# PFIL.net
KiCad netlist of a schematic drawn in Altium Designer
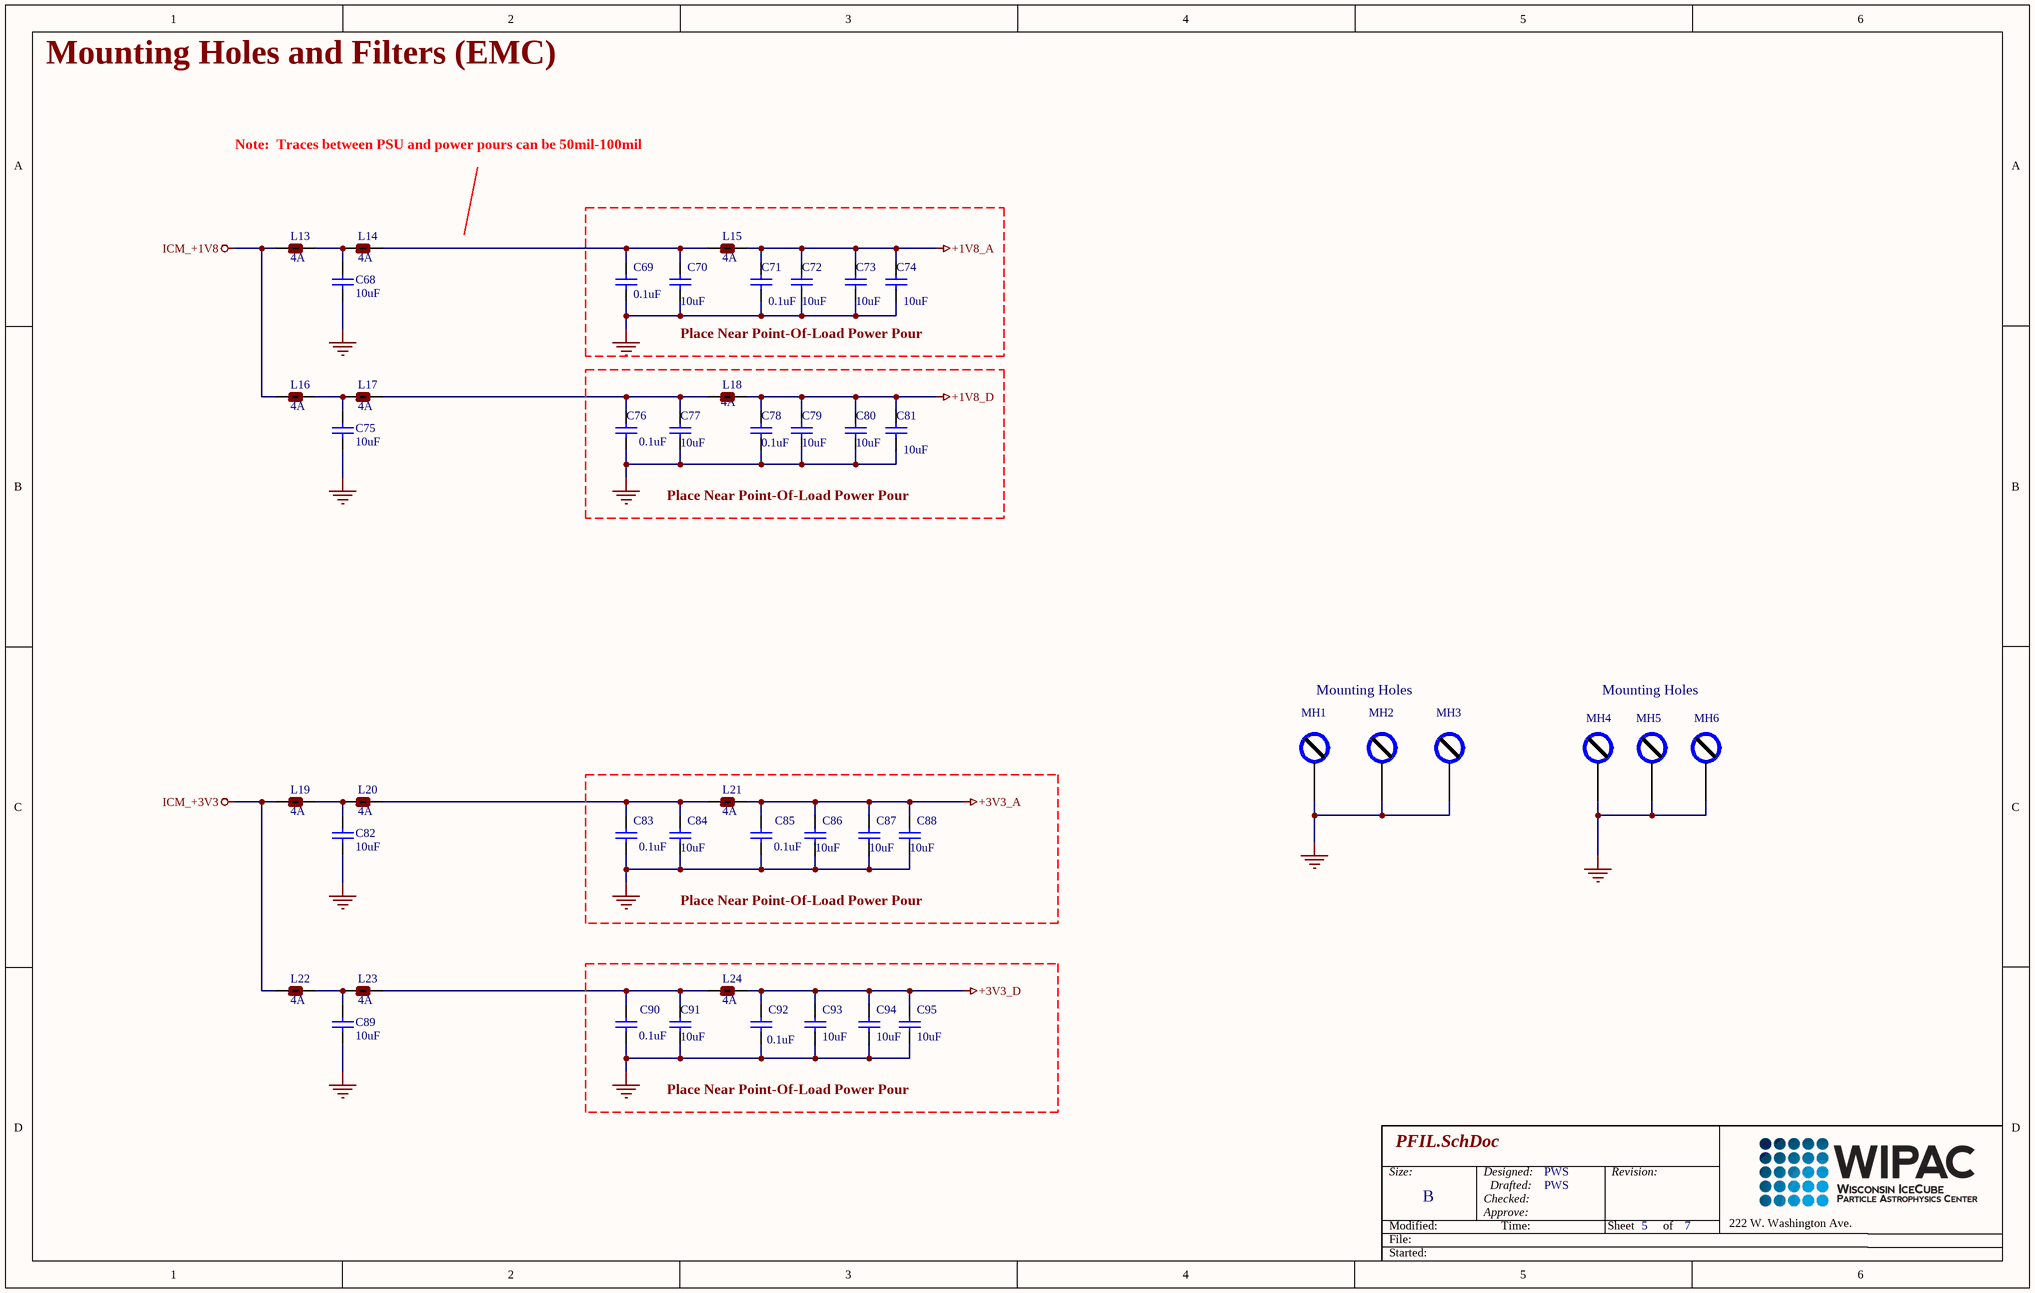
[diagram p0: PFIL.SchDoc]

(export (version "E")
  (design (tool "Eeschema 10.0.6"))
  (components
    (comp (ref "C68")
      (value "10uF_805_10V")
      (footprint "CAPC_0805")
      (description "Capacitor")
      (fields
        (field (name "MANUFACTURER") "Murata")
        (field (name "MANUFACTURER PART NUMBER") "GCJ21BR71A106KE01L")
        (field (name "CAPACITANCE") "10uF")
      )
      (libsource (lib "Custom1") (part "CapC_10uF_805_10V"))
    )
    (comp (ref "C69")
      (value "0.1uF_603_50V")
      (footprint "CAPC_0603")
      (description "0.1µF ±10% 50V Ceramic Capacitor X7R 0603 (1608 Metric)")
      (fields
        (field (name "MANUFACTURER") "Murata")
        (field (name "MANUFACTURER PART NUMBER") "GCJ188R71H104KA12D")
        (field (name "CAPACITANCE") "0.1uF")
      )
      (libsource (lib "Custom1") (part "CapC_0.1uF_603_50V_GCJ"))
    )
    (comp (ref "C70")
      (value "10uF_805_10V")
      (footprint "CAPC_0805")
      (description "Capacitor")
      (fields
        (field (name "MANUFACTURER") "Murata")
        (field (name "MANUFACTURER PART NUMBER") "GCJ21BR71A106KE01L")
        (field (name "CAPACITANCE") "10uF")
      )
      (libsource (lib "Custom1") (part "CapC_10uF_805_10V"))
    )
    (comp (ref "C71")
      (value "0.1uF_603_50V")
      (footprint "CAPC_0603")
      (description "0.1µF ±10% 50V Ceramic Capacitor X7R 0603 (1608 Metric)")
      (fields
        (field (name "MANUFACTURER") "Murata")
        (field (name "MANUFACTURER PART NUMBER") "GCJ188R71H104KA12D")
        (field (name "CAPACITANCE") "0.1uF")
      )
      (libsource (lib "Custom1") (part "CapC_0.1uF_603_50V_GCJ"))
    )
    (comp (ref "C72")
      (value "10uF_805_10V")
      (footprint "CAPC_0805")
      (description "Capacitor")
      (fields
        (field (name "MANUFACTURER") "Murata")
        (field (name "MANUFACTURER PART NUMBER") "GCJ21BR71A106KE01L")
        (field (name "CAPACITANCE") "10uF")
      )
      (libsource (lib "Custom1") (part "CapC_10uF_805_10V"))
    )
    (comp (ref "C73")
      (value "10uF_805_10V")
      (footprint "CAPC_0805")
      (description "Capacitor")
      (fields
        (field (name "MANUFACTURER") "Murata")
        (field (name "MANUFACTURER PART NUMBER") "GCJ21BR71A106KE01L")
        (field (name "CAPACITANCE") "10uF")
      )
      (libsource (lib "Custom1") (part "CapC_10uF_805_10V"))
    )
    (comp (ref "C74")
      (value "10uF_805_10V")
      (footprint "CAPC_0805")
      (description "Capacitor")
      (fields
        (field (name "MANUFACTURER") "Murata")
        (field (name "MANUFACTURER PART NUMBER") "GCJ21BR71A106KE01L")
        (field (name "CAPACITANCE") "10uF")
      )
      (libsource (lib "Custom1") (part "CapC_10uF_805_10V"))
    )
    (comp (ref "C75")
      (value "10uF_805_10V")
      (footprint "CAPC_0805")
      (description "Capacitor")
      (fields
        (field (name "MANUFACTURER") "Murata")
        (field (name "MANUFACTURER PART NUMBER") "GCJ21BR71A106KE01L")
        (field (name "CAPACITANCE") "10uF")
      )
      (libsource (lib "Custom1") (part "CapC_10uF_805_10V"))
    )
    (comp (ref "C76")
      (value "0.1uF_603_50V")
      (footprint "CAPC_0603")
      (description "0.1µF ±10% 50V Ceramic Capacitor X7R 0603 (1608 Metric)")
      (fields
        (field (name "MANUFACTURER") "Murata")
        (field (name "MANUFACTURER PART NUMBER") "GCJ188R71H104KA12D")
        (field (name "CAPACITANCE") "0.1uF")
      )
      (libsource (lib "Custom1") (part "CapC_0.1uF_603_50V_GCJ"))
    )
    (comp (ref "C77")
      (value "10uF_805_10V")
      (footprint "CAPC_0805")
      (description "Capacitor")
      (fields
        (field (name "MANUFACTURER") "Murata")
        (field (name "MANUFACTURER PART NUMBER") "GCJ21BR71A106KE01L")
        (field (name "CAPACITANCE") "10uF")
      )
      (libsource (lib "Custom1") (part "CapC_10uF_805_10V"))
    )
    (comp (ref "C78")
      (value "0.1uF_603_50V")
      (footprint "CAPC_0603")
      (description "0.1µF ±10% 50V Ceramic Capacitor X7R 0603 (1608 Metric)")
      (fields
        (field (name "MANUFACTURER") "Murata")
        (field (name "MANUFACTURER PART NUMBER") "GCJ188R71H104KA12D")
        (field (name "CAPACITANCE") "0.1uF")
      )
      (libsource (lib "Custom1") (part "CapC_0.1uF_603_50V_GCJ"))
    )
    (comp (ref "C79")
      (value "10uF_805_10V")
      (footprint "CAPC_0805")
      (description "Capacitor")
      (fields
        (field (name "MANUFACTURER") "Murata")
        (field (name "MANUFACTURER PART NUMBER") "GCJ21BR71A106KE01L")
        (field (name "CAPACITANCE") "10uF")
      )
      (libsource (lib "Custom1") (part "CapC_10uF_805_10V"))
    )
    (comp (ref "C80")
      (value "10uF_805_10V")
      (footprint "CAPC_0805")
      (description "Capacitor")
      (fields
        (field (name "MANUFACTURER") "Murata")
        (field (name "MANUFACTURER PART NUMBER") "GCJ21BR71A106KE01L")
        (field (name "CAPACITANCE") "10uF")
      )
      (libsource (lib "Custom1") (part "CapC_10uF_805_10V"))
    )
    (comp (ref "C81")
      (value "10uF_805_10V")
      (footprint "CAPC_0805")
      (description "Capacitor")
      (fields
        (field (name "MANUFACTURER") "Murata")
        (field (name "MANUFACTURER PART NUMBER") "GCJ21BR71A106KE01L")
        (field (name "CAPACITANCE") "10uF")
      )
      (libsource (lib "Custom1") (part "CapC_10uF_805_10V"))
    )
    (comp (ref "C82")
      (value "10uF_805_10V")
      (footprint "CAPC_0805")
      (description "Capacitor")
      (fields
        (field (name "MANUFACTURER") "Murata")
        (field (name "MANUFACTURER PART NUMBER") "GCJ21BR71A106KE01L")
        (field (name "CAPACITANCE") "10uF")
      )
      (libsource (lib "Custom1") (part "CapC_10uF_805_10V"))
    )
    (comp (ref "C83")
      (value "0.1uF_603_50V")
      (footprint "CAPC_0603")
      (description "0.1µF ±10% 50V Ceramic Capacitor X7R 0603 (1608 Metric)")
      (fields
        (field (name "MANUFACTURER") "Murata")
        (field (name "MANUFACTURER PART NUMBER") "GCJ188R71H104KA12D")
        (field (name "CAPACITANCE") "0.1uF")
      )
      (libsource (lib "Custom1") (part "CapC_0.1uF_603_50V_GCJ"))
    )
    (comp (ref "C84")
      (value "10uF_805_10V")
      (footprint "CAPC_0805")
      (description "Capacitor")
      (fields
        (field (name "MANUFACTURER") "Murata")
        (field (name "MANUFACTURER PART NUMBER") "GCJ21BR71A106KE01L")
        (field (name "CAPACITANCE") "10uF")
      )
      (libsource (lib "Custom1") (part "CapC_10uF_805_10V"))
    )
    (comp (ref "C85")
      (value "0.1uF_603_50V")
      (footprint "CAPC_0603")
      (description "0.1µF ±10% 50V Ceramic Capacitor X7R 0603 (1608 Metric)")
      (fields
        (field (name "MANUFACTURER") "Murata")
        (field (name "MANUFACTURER PART NUMBER") "GCJ188R71H104KA12D")
        (field (name "CAPACITANCE") "0.1uF")
      )
      (libsource (lib "Custom1") (part "CapC_0.1uF_603_50V_GCJ"))
    )
    (comp (ref "C86")
      (value "10uF_805_10V")
      (footprint "CAPC_0805")
      (description "Capacitor")
      (fields
        (field (name "MANUFACTURER") "Murata")
        (field (name "MANUFACTURER PART NUMBER") "GCJ21BR71A106KE01L")
        (field (name "CAPACITANCE") "10uF")
      )
      (libsource (lib "Custom1") (part "CapC_10uF_805_10V"))
    )
    (comp (ref "C87")
      (value "10uF_805_10V")
      (footprint "CAPC_0805")
      (description "Capacitor")
      (fields
        (field (name "MANUFACTURER") "Murata")
        (field (name "MANUFACTURER PART NUMBER") "GCJ21BR71A106KE01L")
        (field (name "CAPACITANCE") "10uF")
      )
      (libsource (lib "Custom1") (part "CapC_10uF_805_10V"))
    )
    (comp (ref "C88")
      (value "10uF_805_10V")
      (footprint "CAPC_0805")
      (description "Capacitor")
      (fields
        (field (name "MANUFACTURER") "Murata")
        (field (name "MANUFACTURER PART NUMBER") "GCJ21BR71A106KE01L")
        (field (name "CAPACITANCE") "10uF")
      )
      (libsource (lib "Custom1") (part "CapC_10uF_805_10V"))
    )
    (comp (ref "C89")
      (value "10uF_805_10V")
      (footprint "CAPC_0805")
      (description "Capacitor")
      (fields
        (field (name "MANUFACTURER") "Murata")
        (field (name "MANUFACTURER PART NUMBER") "GCJ21BR71A106KE01L")
        (field (name "CAPACITANCE") "10uF")
      )
      (libsource (lib "Custom1") (part "CapC_10uF_805_10V"))
    )
    (comp (ref "C90")
      (value "0.1uF_603_50V")
      (footprint "CAPC_0603")
      (description "0.1µF ±10% 50V Ceramic Capacitor X7R 0603 (1608 Metric)")
      (fields
        (field (name "MANUFACTURER") "Murata")
        (field (name "MANUFACTURER PART NUMBER") "GCJ188R71H104KA12D")
        (field (name "CAPACITANCE") "0.1uF")
      )
      (libsource (lib "Custom1") (part "CapC_0.1uF_603_50V_GCJ"))
    )
    (comp (ref "C91")
      (value "10uF_805_10V")
      (footprint "CAPC_0805")
      (description "Capacitor")
      (fields
        (field (name "MANUFACTURER") "Murata")
        (field (name "MANUFACTURER PART NUMBER") "GCJ21BR71A106KE01L")
        (field (name "CAPACITANCE") "10uF")
      )
      (libsource (lib "Custom1") (part "CapC_10uF_805_10V"))
    )
    (comp (ref "C92")
      (value "0.1uF_603_50V")
      (footprint "CAPC_0603")
      (description "0.1µF ±10% 50V Ceramic Capacitor X7R 0603 (1608 Metric)")
      (fields
        (field (name "MANUFACTURER") "Murata")
        (field (name "MANUFACTURER PART NUMBER") "GCJ188R71H104KA12D")
        (field (name "CAPACITANCE") "0.1uF")
      )
      (libsource (lib "Custom1") (part "CapC_0.1uF_603_50V_GCJ"))
    )
    (comp (ref "C93")
      (value "10uF_805_10V")
      (footprint "CAPC_0805")
      (description "Capacitor")
      (fields
        (field (name "MANUFACTURER") "Murata")
        (field (name "MANUFACTURER PART NUMBER") "GCJ21BR71A106KE01L")
        (field (name "CAPACITANCE") "10uF")
      )
      (libsource (lib "Custom1") (part "CapC_10uF_805_10V"))
    )
    (comp (ref "C94")
      (value "10uF_805_10V")
      (footprint "CAPC_0805")
      (description "Capacitor")
      (fields
        (field (name "MANUFACTURER") "Murata")
        (field (name "MANUFACTURER PART NUMBER") "GCJ21BR71A106KE01L")
        (field (name "CAPACITANCE") "10uF")
      )
      (libsource (lib "Custom1") (part "CapC_10uF_805_10V"))
    )
    (comp (ref "C95")
      (value "10uF_805_10V")
      (footprint "CAPC_0805")
      (description "Capacitor")
      (fields
        (field (name "MANUFACTURER") "Murata")
        (field (name "MANUFACTURER PART NUMBER") "GCJ21BR71A106KE01L")
        (field (name "CAPACITANCE") "10uF")
      )
      (libsource (lib "Custom1") (part "CapC_10uF_805_10V"))
    )
    (comp (ref "L13")
      (value "4.0A_Bead_0805")
      (footprint "SMD-0805")
      (description "100 Ohms @ 100MHz 1 Power Line Ferrite Bead 0805 (2012 Metric) 4A 20mOhm")
      (fields
        (field (name "MANUFACTURER") "TDK")
        (field (name "MANUFACTURER PART NUMBER") "MPZ2012S101ATD25")
        (field (name "MAX DC CURRENT") "4A")
      )
      (libsource (lib "Custom1") (part "Bead SM_805_4.0A_TDK"))
    )
    (comp (ref "L14")
      (value "4.0A_Bead_0805")
      (footprint "SMD-0805")
      (description "100 Ohms @ 100MHz 1 Power Line Ferrite Bead 0805 (2012 Metric) 4A 20mOhm")
      (fields
        (field (name "MANUFACTURER") "TDK")
        (field (name "MANUFACTURER PART NUMBER") "MPZ2012S101ATD25")
        (field (name "MAX DC CURRENT") "4A")
      )
      (libsource (lib "Custom1") (part "Bead SM_805_4.0A_TDK"))
    )
    (comp (ref "L15")
      (value "4.0A_Bead_0805")
      (footprint "SMD-0805")
      (description "100 Ohms @ 100MHz 1 Power Line Ferrite Bead 0805 (2012 Metric) 4A 20mOhm")
      (fields
        (field (name "MANUFACTURER") "TDK")
        (field (name "MANUFACTURER PART NUMBER") "MPZ2012S101ATD25")
        (field (name "MAX DC CURRENT") "4A")
      )
      (libsource (lib "Custom1") (part "Bead SM_805_4.0A_TDK"))
    )
    (comp (ref "L16")
      (value "4.0A_Bead_0805")
      (footprint "SMD-0805")
      (description "100 Ohms @ 100MHz 1 Power Line Ferrite Bead 0805 (2012 Metric) 4A 20mOhm")
      (fields
        (field (name "MANUFACTURER") "TDK")
        (field (name "MANUFACTURER PART NUMBER") "MPZ2012S101ATD25")
        (field (name "MAX DC CURRENT") "4A")
      )
      (libsource (lib "Custom1") (part "Bead SM_805_4.0A_TDK"))
    )
    (comp (ref "L17")
      (value "4.0A_Bead_0805")
      (footprint "SMD-0805")
      (description "100 Ohms @ 100MHz 1 Power Line Ferrite Bead 0805 (2012 Metric) 4A 20mOhm")
      (fields
        (field (name "MANUFACTURER") "TDK")
        (field (name "MANUFACTURER PART NUMBER") "MPZ2012S101ATD25")
        (field (name "MAX DC CURRENT") "4A")
      )
      (libsource (lib "Custom1") (part "Bead SM_805_4.0A_TDK"))
    )
    (comp (ref "L18")
      (value "4.0A_Bead_0805")
      (footprint "SMD-0805")
      (description "100 Ohms @ 100MHz 1 Power Line Ferrite Bead 0805 (2012 Metric) 4A 20mOhm")
      (fields
        (field (name "MANUFACTURER") "TDK")
        (field (name "MANUFACTURER PART NUMBER") "MPZ2012S101ATD25")
        (field (name "MAX DC CURRENT") "4A")
      )
      (libsource (lib "Custom1") (part "Bead SM_805_4.0A_TDK"))
    )
    (comp (ref "L19")
      (value "4.0A_Bead_0805")
      (footprint "SMD-0805")
      (description "100 Ohms @ 100MHz 1 Power Line Ferrite Bead 0805 (2012 Metric) 4A 20mOhm")
      (fields
        (field (name "MANUFACTURER") "TDK")
        (field (name "MANUFACTURER PART NUMBER") "MPZ2012S101ATD25")
        (field (name "MAX DC CURRENT") "4A")
      )
      (libsource (lib "Custom1") (part "Bead SM_805_4.0A_TDK"))
    )
    (comp (ref "L20")
      (value "4.0A_Bead_0805")
      (footprint "SMD-0805")
      (description "100 Ohms @ 100MHz 1 Power Line Ferrite Bead 0805 (2012 Metric) 4A 20mOhm")
      (fields
        (field (name "MANUFACTURER") "TDK")
        (field (name "MANUFACTURER PART NUMBER") "MPZ2012S101ATD25")
        (field (name "MAX DC CURRENT") "4A")
      )
      (libsource (lib "Custom1") (part "Bead SM_805_4.0A_TDK"))
    )
    (comp (ref "L21")
      (value "4.0A_Bead_0805")
      (footprint "SMD-0805")
      (description "100 Ohms @ 100MHz 1 Power Line Ferrite Bead 0805 (2012 Metric) 4A 20mOhm")
      (fields
        (field (name "MANUFACTURER") "TDK")
        (field (name "MANUFACTURER PART NUMBER") "MPZ2012S101ATD25")
        (field (name "MAX DC CURRENT") "4A")
      )
      (libsource (lib "Custom1") (part "Bead SM_805_4.0A_TDK"))
    )
    (comp (ref "L22")
      (value "4.0A_Bead_0805")
      (footprint "SMD-0805")
      (description "100 Ohms @ 100MHz 1 Power Line Ferrite Bead 0805 (2012 Metric) 4A 20mOhm")
      (fields
        (field (name "MANUFACTURER") "TDK")
        (field (name "MANUFACTURER PART NUMBER") "MPZ2012S101ATD25")
        (field (name "MAX DC CURRENT") "4A")
      )
      (libsource (lib "Custom1") (part "Bead SM_805_4.0A_TDK"))
    )
    (comp (ref "L23")
      (value "4.0A_Bead_0805")
      (footprint "SMD-0805")
      (description "100 Ohms @ 100MHz 1 Power Line Ferrite Bead 0805 (2012 Metric) 4A 20mOhm")
      (fields
        (field (name "MANUFACTURER") "TDK")
        (field (name "MANUFACTURER PART NUMBER") "MPZ2012S101ATD25")
        (field (name "MAX DC CURRENT") "4A")
      )
      (libsource (lib "Custom1") (part "Bead SM_805_4.0A_TDK"))
    )
    (comp (ref "L24")
      (value "4.0A_Bead_0805")
      (footprint "SMD-0805")
      (description "100 Ohms @ 100MHz 1 Power Line Ferrite Bead 0805 (2012 Metric) 4A 20mOhm")
      (fields
        (field (name "MANUFACTURER") "TDK")
        (field (name "MANUFACTURER PART NUMBER") "MPZ2012S101ATD25")
        (field (name "MAX DC CURRENT") "4A")
      )
      (libsource (lib "Custom1") (part "Bead SM_805_4.0A_TDK"))
    )
    (comp (ref "MH1")
      (value "Mounting Hole")
      (footprint "Mounting Pad #4 - Standoff")
      (libsource (lib "Custom1") (part "Mounting Hole #4_Standoff"))
    )
    (comp (ref "MH2")
      (value "Mounting Hole")
      (footprint "Mounting Pad #4 - Standoff")
      (libsource (lib "Custom1") (part "Mounting Hole #4_Standoff"))
    )
    (comp (ref "MH3")
      (value "Mounting Hole")
      (footprint "Mounting Pad #4 - Standoff")
      (libsource (lib "Custom1") (part "Mounting Hole #4_Standoff"))
    )
    (comp (ref "MH4")
      (value "Mounting Hole")
      (footprint "Mounting Pad #4 - Standoff")
      (libsource (lib "Custom1") (part "Mounting Hole #4_Standoff"))
    )
    (comp (ref "MH5")
      (value "Mounting Hole")
      (footprint "Mounting Pad #4 - Standoff")
      (libsource (lib "Custom1") (part "Mounting Hole #4_Standoff"))
    )
    (comp (ref "MH6")
      (value "Mounting Hole")
      (footprint "Mounting Pad #4 - Standoff")
      (libsource (lib "Custom1") (part "Mounting Hole #4_Standoff"))
    )
  )
  (nets
    (net (code "1") (name "+1V8_A") (class "Default")
      (node (ref "C71") (pin "2") (pinfunction "2_2") (pintype "passive"))
      (node (ref "C72") (pin "2") (pinfunction "2_2") (pintype "passive"))
      (node (ref "C73") (pin "2") (pinfunction "2_2") (pintype "passive"))
      (node (ref "C74") (pin "2") (pinfunction "2_2") (pintype "passive"))
      (node (ref "L15") (pin "2") (pinfunction "2_2") (pintype "passive"))
    )
    (net (code "2") (name "+1V8_D") (class "Default")
      (node (ref "C78") (pin "2") (pinfunction "2_2") (pintype "passive"))
      (node (ref "C79") (pin "2") (pinfunction "2_2") (pintype "passive"))
      (node (ref "C80") (pin "2") (pinfunction "2_2") (pintype "passive"))
      (node (ref "C81") (pin "2") (pinfunction "2_2") (pintype "passive"))
      (node (ref "L18") (pin "2") (pinfunction "2_2") (pintype "passive"))
    )
    (net (code "3") (name "+3V3_A") (class "Default")
      (node (ref "C85") (pin "2") (pinfunction "2_2") (pintype "passive"))
      (node (ref "C86") (pin "2") (pinfunction "2_2") (pintype "passive"))
      (node (ref "C87") (pin "2") (pinfunction "2_2") (pintype "passive"))
      (node (ref "C88") (pin "2") (pinfunction "2_2") (pintype "passive"))
      (node (ref "L21") (pin "2") (pinfunction "2_2") (pintype "passive"))
    )
    (net (code "4") (name "+3V3_D") (class "Default")
      (node (ref "C92") (pin "2") (pinfunction "2_2") (pintype "passive"))
      (node (ref "C93") (pin "2") (pinfunction "2_2") (pintype "passive"))
      (node (ref "C94") (pin "2") (pinfunction "2_2") (pintype "passive"))
      (node (ref "C95") (pin "2") (pinfunction "2_2") (pintype "passive"))
      (node (ref "L24") (pin "2") (pinfunction "2_2") (pintype "passive"))
    )
    (net (code "5") (name "GND") (class "Default")
      (node (ref "C68") (pin "1") (pinfunction "1_1") (pintype "passive"))
      (node (ref "C69") (pin "1") (pinfunction "1_1") (pintype "passive"))
      (node (ref "C70") (pin "1") (pinfunction "1_1") (pintype "passive"))
      (node (ref "C71") (pin "1") (pinfunction "1_1") (pintype "passive"))
      (node (ref "C72") (pin "1") (pinfunction "1_1") (pintype "passive"))
      (node (ref "C73") (pin "1") (pinfunction "1_1") (pintype "passive"))
      (node (ref "C74") (pin "1") (pinfunction "1_1") (pintype "passive"))
      (node (ref "C75") (pin "1") (pinfunction "1_1") (pintype "passive"))
      (node (ref "C76") (pin "1") (pinfunction "1_1") (pintype "passive"))
      (node (ref "C77") (pin "1") (pinfunction "1_1") (pintype "passive"))
      (node (ref "C78") (pin "1") (pinfunction "1_1") (pintype "passive"))
      (node (ref "C79") (pin "1") (pinfunction "1_1") (pintype "passive"))
      (node (ref "C80") (pin "1") (pinfunction "1_1") (pintype "passive"))
      (node (ref "C81") (pin "1") (pinfunction "1_1") (pintype "passive"))
      (node (ref "C82") (pin "1") (pinfunction "1_1") (pintype "passive"))
      (node (ref "C83") (pin "1") (pinfunction "1_1") (pintype "passive"))
      (node (ref "C84") (pin "1") (pinfunction "1_1") (pintype "passive"))
      (node (ref "C85") (pin "1") (pinfunction "1_1") (pintype "passive"))
      (node (ref "C86") (pin "1") (pinfunction "1_1") (pintype "passive"))
      (node (ref "C87") (pin "1") (pinfunction "1_1") (pintype "passive"))
      (node (ref "C88") (pin "1") (pinfunction "1_1") (pintype "passive"))
      (node (ref "C89") (pin "1") (pinfunction "1_1") (pintype "passive"))
      (node (ref "C90") (pin "1") (pinfunction "1_1") (pintype "passive"))
      (node (ref "C91") (pin "1") (pinfunction "1_1") (pintype "passive"))
      (node (ref "C92") (pin "1") (pinfunction "1_1") (pintype "passive"))
      (node (ref "C93") (pin "1") (pinfunction "1_1") (pintype "passive"))
      (node (ref "C94") (pin "1") (pinfunction "1_1") (pintype "passive"))
      (node (ref "C95") (pin "1") (pinfunction "1_1") (pintype "passive"))
      (node (ref "MH1") (pin "0") (pinfunction "0_0") (pintype "passive"))
      (node (ref "MH2") (pin "0") (pinfunction "0_0") (pintype "passive"))
      (node (ref "MH3") (pin "0") (pinfunction "0_0") (pintype "passive"))
      (node (ref "MH4") (pin "0") (pinfunction "0_0") (pintype "passive"))
      (node (ref "MH5") (pin "0") (pinfunction "0_0") (pintype "passive"))
      (node (ref "MH6") (pin "0") (pinfunction "0_0") (pintype "passive"))
    )
    (net (code "6") (name "ICM_+1V8") (class "Default")
      (node (ref "L13") (pin "1") (pinfunction "1_1") (pintype "passive"))
      (node (ref "L16") (pin "1") (pinfunction "1_1") (pintype "passive"))
    )
    (net (code "7") (name "ICM_+3V3") (class "Default")
      (node (ref "L19") (pin "1") (pinfunction "1_1") (pintype "passive"))
      (node (ref "L22") (pin "1") (pinfunction "1_1") (pintype "passive"))
    )
    (net (code "8") (name "Net-(C68-Pad2)") (class "Default")
      (node (ref "C68") (pin "2") (pinfunction "2_2") (pintype "passive"))
      (node (ref "L13") (pin "2") (pinfunction "2_2") (pintype "passive"))
      (node (ref "L14") (pin "1") (pinfunction "1_1") (pintype "passive"))
    )
    (net (code "9") (name "Net-(C69-Pad2)") (class "Default")
      (node (ref "C69") (pin "2") (pinfunction "2_2") (pintype "passive"))
      (node (ref "C70") (pin "2") (pinfunction "2_2") (pintype "passive"))
      (node (ref "L14") (pin "2") (pinfunction "2_2") (pintype "passive"))
      (node (ref "L15") (pin "1") (pinfunction "1_1") (pintype "passive"))
    )
    (net (code "10") (name "Net-(C75-Pad2)") (class "Default")
      (node (ref "C75") (pin "2") (pinfunction "2_2") (pintype "passive"))
      (node (ref "L16") (pin "2") (pinfunction "2_2") (pintype "passive"))
      (node (ref "L17") (pin "1") (pinfunction "1_1") (pintype "passive"))
    )
    (net (code "11") (name "Net-(C76-Pad2)") (class "Default")
      (node (ref "C76") (pin "2") (pinfunction "2_2") (pintype "passive"))
      (node (ref "C77") (pin "2") (pinfunction "2_2") (pintype "passive"))
      (node (ref "L17") (pin "2") (pinfunction "2_2") (pintype "passive"))
      (node (ref "L18") (pin "1") (pinfunction "1_1") (pintype "passive"))
    )
    (net (code "12") (name "Net-(C82-Pad2)") (class "Default")
      (node (ref "C82") (pin "2") (pinfunction "2_2") (pintype "passive"))
      (node (ref "L19") (pin "2") (pinfunction "2_2") (pintype "passive"))
      (node (ref "L20") (pin "1") (pinfunction "1_1") (pintype "passive"))
    )
    (net (code "13") (name "Net-(C83-Pad2)") (class "Default")
      (node (ref "C83") (pin "2") (pinfunction "2_2") (pintype "passive"))
      (node (ref "C84") (pin "2") (pinfunction "2_2") (pintype "passive"))
      (node (ref "L20") (pin "2") (pinfunction "2_2") (pintype "passive"))
      (node (ref "L21") (pin "1") (pinfunction "1_1") (pintype "passive"))
    )
    (net (code "14") (name "Net-(C89-Pad2)") (class "Default")
      (node (ref "C89") (pin "2") (pinfunction "2_2") (pintype "passive"))
      (node (ref "L22") (pin "2") (pinfunction "2_2") (pintype "passive"))
      (node (ref "L23") (pin "1") (pinfunction "1_1") (pintype "passive"))
    )
    (net (code "15") (name "Net-(C90-Pad2)") (class "Default")
      (node (ref "C90") (pin "2") (pinfunction "2_2") (pintype "passive"))
      (node (ref "C91") (pin "2") (pinfunction "2_2") (pintype "passive"))
      (node (ref "L23") (pin "2") (pinfunction "2_2") (pintype "passive"))
      (node (ref "L24") (pin "1") (pinfunction "1_1") (pintype "passive"))
    )
  )
)
